# naswietlarka.net
KiCad netlist of a schematic drawn in EAGLE
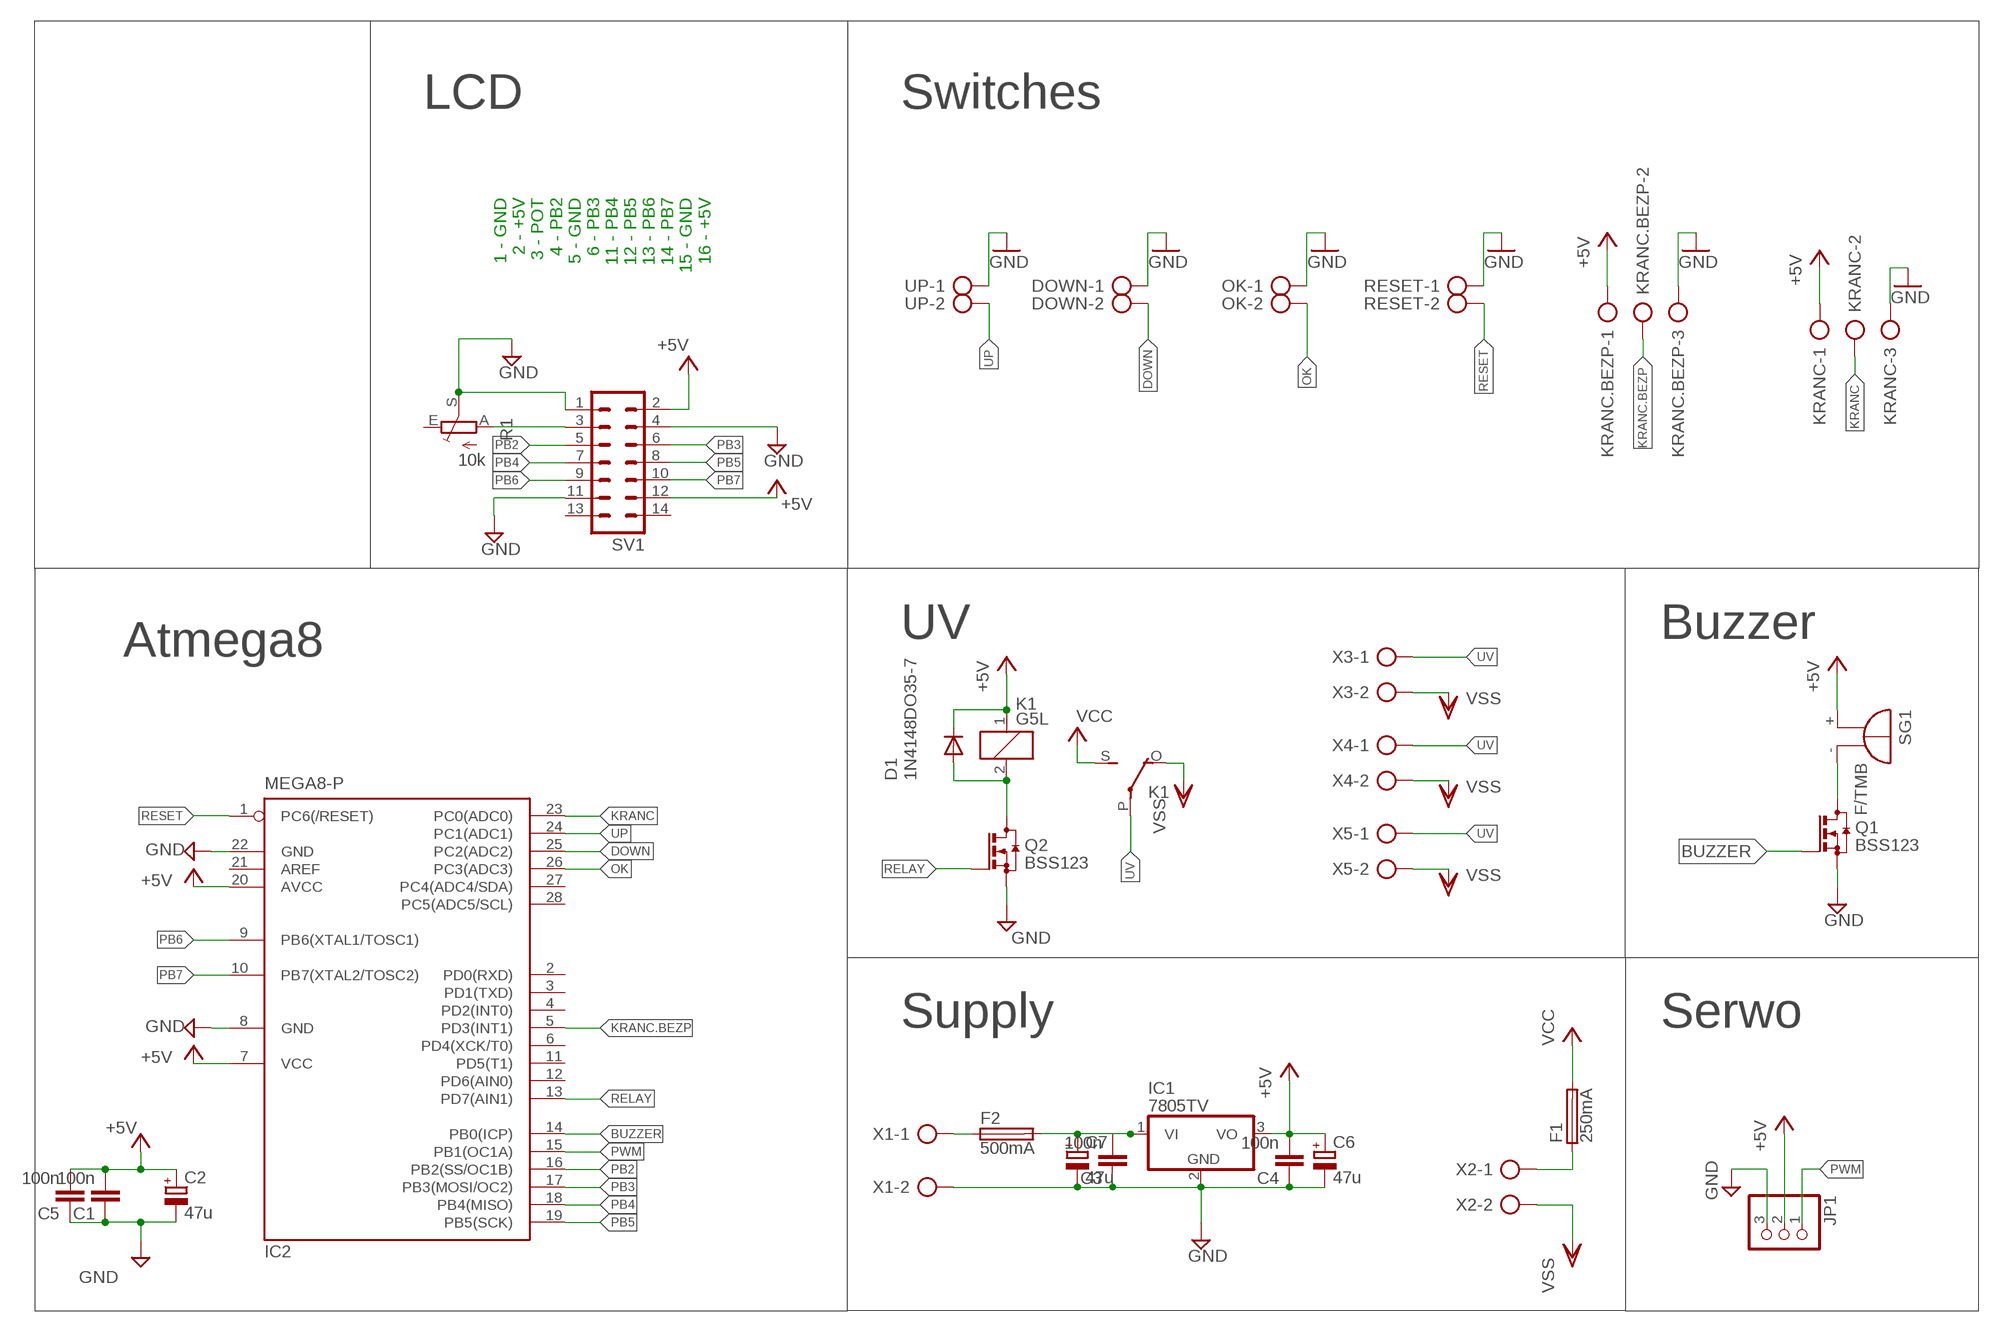
[diagram p0: schematic, sheet 1]

(export (version "E")
  (design (tool "Eeschema 10.0.6"))
  (components
    (comp (ref "C1")
      (value "100n")
      (footprint "eagle-import:C0805")
      (libsource (lib "eagle-import") (part "C-EUC0805"))
    )
    (comp (ref "C2")
      (value "47u")
      (footprint "eagle-import:E2,5-5")
      (libsource (lib "eagle-import") (part "CPOL-EUE2.5-5"))
    )
    (comp (ref "C3")
      (value "100n")
      (footprint "eagle-import:C0805")
      (libsource (lib "eagle-import") (part "C-EUC0805"))
    )
    (comp (ref "C4")
      (value "100n")
      (footprint "eagle-import:C0805")
      (libsource (lib "eagle-import") (part "C-EUC0805"))
    )
    (comp (ref "C5")
      (value "100n")
      (footprint "eagle-import:C0805")
      (libsource (lib "eagle-import") (part "C-EUC0805"))
    )
    (comp (ref "C6")
      (value "47u")
      (footprint "eagle-import:E2,5-5")
      (libsource (lib "eagle-import") (part "CPOL-EUE2.5-5"))
    )
    (comp (ref "C7")
      (value "47u")
      (footprint "eagle-import:E2,5-5")
      (libsource (lib "eagle-import") (part "CPOL-EUE2.5-5"))
    )
    (comp (ref "D1")
      (value "1N4148DO35-7")
      (footprint "eagle-import:DO35-7")
      (libsource (lib "eagle-import") (part "1N4148DO35-7"))
    )
    (comp (ref "DOWN")
      (value "AK300/2")
      (footprint "eagle-import:AK300_2")
      (libsource (lib "eagle-import") (part "AK300/2"))
    )
    (comp (ref "F1")
      (value "250mA")
      (footprint "eagle-import:SH22,5")
      (fields (field (name "MF") "SCHURTER") (field (name "MPN") "0031.8201"))
      (libsource (lib "eagle-import") (part "SH22,5"))
    )
    (comp (ref "F2")
      (value "500mA")
      (footprint "eagle-import:SH22,5")
      (fields (field (name "MF") "SCHURTER") (field (name "MPN") "0031.8201"))
      (libsource (lib "eagle-import") (part "SH22,5"))
    )
    (comp (ref "IC1")
      (value "7805TV")
      (footprint "eagle-import:TO220V")
      (libsource (lib "eagle-import") (part "78TV05"))
    )
    (comp (ref "IC2")
      (value "MEGA8-P")
      (footprint "eagle-import:DIL28-3")
      (libsource (lib "eagle-import") (part "MEGA8-P"))
    )
    (comp (ref "JP1")
      (value "PINHD-1X3")
      (footprint "eagle-import:1X03")
      (libsource (lib "eagle-import") (part "PINHD-1X3"))
    )
    (comp (ref "K1")
      (value "G5L")
      (footprint "eagle-import:G5LE")
      (libsource (lib "eagle-import") (part "G5L"))
    )
    (comp (ref "KRANC")
      (value "AK300/3")
      (footprint "eagle-import:AK300_3")
      (libsource (lib "eagle-import") (part "AK300/3"))
    )
    (comp (ref "KRANC.BEZP")
      (value "AK300/3")
      (footprint "eagle-import:AK300_3")
      (libsource (lib "eagle-import") (part "AK300/3"))
    )
    (comp (ref "OK")
      (value "AK300/2")
      (footprint "eagle-import:AK300_2")
      (libsource (lib "eagle-import") (part "AK300/2"))
    )
    (comp (ref "Q1")
      (value "BSS123")
      (footprint "eagle-import:SOT23")
      (libsource (lib "eagle-import") (part "BSS123"))
    )
    (comp (ref "Q2")
      (value "BSS123")
      (footprint "eagle-import:SOT23")
      (libsource (lib "eagle-import") (part "BSS123"))
    )
    (comp (ref "R1")
      (value "10k")
      (footprint "eagle-import:CA6V")
      (libsource (lib "eagle-import") (part "TRIM_EU-CA6V"))
    )
    (comp (ref "RESET")
      (value "AK300/2")
      (footprint "eagle-import:AK300_2")
      (libsource (lib "eagle-import") (part "AK300/2"))
    )
    (comp (ref "SG1")
      (value "F/TMB")
      (footprint "eagle-import:F_TMB")
      (libsource (lib "eagle-import") (part "F/TMB"))
    )
    (comp (ref "SV1")
      (value "ML14")
      (footprint "eagle-import:ML14")
      (libsource (lib "eagle-import") (part "ML14"))
    )
    (comp (ref "UP")
      (value "AK300/2")
      (footprint "eagle-import:AK300_2")
      (libsource (lib "eagle-import") (part "AK300/2"))
    )
    (comp (ref "X1")
      (value "AK500/2-H")
      (footprint "eagle-import:AK500_2-H")
      (libsource (lib "eagle-import") (part "AK500/2-H"))
    )
    (comp (ref "X2")
      (value "AK500/2-H")
      (footprint "eagle-import:AK500_2-H")
      (libsource (lib "eagle-import") (part "AK500/2-H"))
    )
    (comp (ref "X3")
      (value "AK500/2-H")
      (footprint "eagle-import:AK500_2-H")
      (libsource (lib "eagle-import") (part "AK500/2-H"))
    )
    (comp (ref "X4")
      (value "AK500/2-H")
      (footprint "eagle-import:AK500_2-H")
      (libsource (lib "eagle-import") (part "AK500/2-H"))
    )
    (comp (ref "X5")
      (value "AK500/2-H")
      (footprint "eagle-import:AK500_2-H")
      (libsource (lib "eagle-import") (part "AK500/2-H"))
    )
  )
  (nets
    (net (code "1") (name "+5V") (class "Default")
      (node (ref "C1") (pin "2") (pinfunction "2_2") (pintype "passive"))
      (node (ref "C2") (pin "+") (pinfunction "+_+") (pintype "passive"))
      (node (ref "C4") (pin "2") (pinfunction "2_2") (pintype "passive"))
      (node (ref "C5") (pin "2") (pinfunction "2_2") (pintype "passive"))
      (node (ref "C6") (pin "+") (pinfunction "+_+") (pintype "passive"))
      (node (ref "D1") (pin "C") (pinfunction "C_C") (pintype "passive"))
      (node (ref "IC1") (pin "3") (pinfunction "VO_3") (pintype "passive"))
      (node (ref "IC2") (pin "20") (pinfunction "AVCC_20") (pintype "power_in"))
      (node (ref "IC2") (pin "7") (pinfunction "VCC_7") (pintype "power_in"))
      (node (ref "JP1") (pin "2") (pinfunction "2_2") (pintype "passive"))
      (node (ref "K1") (pin "1") (pinfunction "1_1") (pintype "passive"))
      (node (ref "KRANC") (pin "1") (pinfunction "KL_1") (pintype "passive"))
      (node (ref "KRANC.BEZP") (pin "1") (pinfunction "KL_1") (pintype "passive"))
      (node (ref "SG1") (pin "+") (pinfunction "+_+") (pintype "passive"))
      (node (ref "SV1") (pin "12") (pinfunction "12_12") (pintype "passive"))
      (node (ref "SV1") (pin "2") (pinfunction "2_2") (pintype "passive"))
    )
    (net (code "2") (name "BUZZER") (class "Default")
      (node (ref "IC2") (pin "14") (pinfunction "PB0(ICP)_14") (pintype "bidirectional"))
      (node (ref "Q1") (pin "1") (pinfunction "G_1") (pintype "passive"))
    )
    (net (code "3") (name "DOWN") (class "Default")
      (node (ref "DOWN") (pin "2") (pinfunction "KL_2") (pintype "passive"))
      (node (ref "IC2") (pin "25") (pinfunction "PC2(ADC2)_25") (pintype "bidirectional"))
    )
    (net (code "4") (name "GND") (class "Default")
      (node (ref "C1") (pin "1") (pinfunction "1_1") (pintype "passive"))
      (node (ref "C2") (pin "-") (pinfunction "-_-") (pintype "passive"))
      (node (ref "C3") (pin "1") (pinfunction "1_1") (pintype "passive"))
      (node (ref "C4") (pin "1") (pinfunction "1_1") (pintype "passive"))
      (node (ref "C5") (pin "1") (pinfunction "1_1") (pintype "passive"))
      (node (ref "C6") (pin "-") (pinfunction "-_-") (pintype "passive"))
      (node (ref "C7") (pin "-") (pinfunction "-_-") (pintype "passive"))
      (node (ref "DOWN") (pin "1") (pinfunction "KL_1") (pintype "passive"))
      (node (ref "IC1") (pin "2") (pinfunction "GND_2") (pintype "passive"))
      (node (ref "IC2") (pin "22") (pinfunction "GND_22") (pintype "power_in"))
      (node (ref "IC2") (pin "8") (pinfunction "GND_8") (pintype "power_in"))
      (node (ref "JP1") (pin "3") (pinfunction "3_3") (pintype "passive"))
      (node (ref "KRANC") (pin "3") (pinfunction "KL_3") (pintype "passive"))
      (node (ref "KRANC.BEZP") (pin "3") (pinfunction "KL_3") (pintype "passive"))
      (node (ref "OK") (pin "1") (pinfunction "KL_1") (pintype "passive"))
      (node (ref "Q1") (pin "2") (pinfunction "S_2") (pintype "passive"))
      (node (ref "Q2") (pin "2") (pinfunction "S_2") (pintype "passive"))
      (node (ref "R1") (pin "S") (pinfunction "S_S") (pintype "passive"))
      (node (ref "RESET") (pin "1") (pinfunction "KL_1") (pintype "passive"))
      (node (ref "SV1") (pin "1") (pinfunction "1_1") (pintype "passive"))
      (node (ref "SV1") (pin "11") (pinfunction "11_11") (pintype "passive"))
      (node (ref "SV1") (pin "4") (pinfunction "4_4") (pintype "passive"))
      (node (ref "UP") (pin "1") (pinfunction "KL_1") (pintype "passive"))
      (node (ref "X1") (pin "2") (pinfunction "KL_2") (pintype "passive"))
    )
    (net (code "5") (name "KRANC") (class "Default")
      (node (ref "IC2") (pin "23") (pinfunction "PC0(ADC0)_23") (pintype "bidirectional"))
      (node (ref "KRANC") (pin "2") (pinfunction "KL_2") (pintype "passive"))
    )
    (net (code "6") (name "KRANC.BEZP") (class "Default")
      (node (ref "IC2") (pin "5") (pinfunction "PD3(INT1)_5") (pintype "bidirectional"))
      (node (ref "KRANC.BEZP") (pin "2") (pinfunction "KL_2") (pintype "passive"))
    )
    (net (code "7") (name "Net-(IC1-VI)") (class "Default")
      (node (ref "C3") (pin "2") (pinfunction "2_2") (pintype "passive"))
      (node (ref "C7") (pin "+") (pinfunction "+_+") (pintype "passive"))
      (node (ref "F2") (pin "2") (pinfunction "2_2") (pintype "passive"))
      (node (ref "IC1") (pin "1") (pinfunction "VI_1") (pintype "input"))
    )
    (net (code "8") (name "Net-(Q1-D)") (class "Default")
      (node (ref "Q1") (pin "3") (pinfunction "D_3") (pintype "passive"))
      (node (ref "SG1") (pin "-") (pinfunction "-_-") (pintype "passive"))
    )
    (net (code "9") (name "Net-(Q2-D)") (class "Default")
      (node (ref "D1") (pin "A") (pinfunction "A_A") (pintype "passive"))
      (node (ref "K1") (pin "2") (pinfunction "2_2") (pintype "passive"))
      (node (ref "Q2") (pin "3") (pinfunction "D_3") (pintype "passive"))
    )
    (net (code "10") (name "Net-(R1-PadA)") (class "Default")
      (node (ref "R1") (pin "A") (pinfunction "A_A") (pintype "passive"))
      (node (ref "SV1") (pin "3") (pinfunction "3_3") (pintype "passive"))
    )
    (net (code "11") (name "Net-(X1A-KL)") (class "Default")
      (node (ref "F2") (pin "1") (pinfunction "1_1") (pintype "passive"))
      (node (ref "X1") (pin "1") (pinfunction "KL_1") (pintype "passive"))
    )
    (net (code "12") (name "Net-(X2A-KL)") (class "Default")
      (node (ref "F1") (pin "1") (pinfunction "1_1") (pintype "passive"))
      (node (ref "X2") (pin "1") (pinfunction "KL_1") (pintype "passive"))
    )
    (net (code "13") (name "OK") (class "Default")
      (node (ref "IC2") (pin "26") (pinfunction "PC3(ADC3)_26") (pintype "bidirectional"))
      (node (ref "OK") (pin "2") (pinfunction "KL_2") (pintype "passive"))
    )
    (net (code "14") (name "PB2") (class "Default")
      (node (ref "IC2") (pin "16") (pinfunction "PB2(SS/OC1B)_16") (pintype "bidirectional"))
      (node (ref "SV1") (pin "5") (pinfunction "5_5") (pintype "passive"))
    )
    (net (code "15") (name "PB3") (class "Default")
      (node (ref "IC2") (pin "17") (pinfunction "PB3(MOSI/OC2)_17") (pintype "bidirectional"))
      (node (ref "SV1") (pin "6") (pinfunction "6_6") (pintype "passive"))
    )
    (net (code "16") (name "PB4") (class "Default")
      (node (ref "IC2") (pin "18") (pinfunction "PB4(MISO)_18") (pintype "bidirectional"))
      (node (ref "SV1") (pin "7") (pinfunction "7_7") (pintype "passive"))
    )
    (net (code "17") (name "PB5") (class "Default")
      (node (ref "IC2") (pin "19") (pinfunction "PB5(SCK)_19") (pintype "bidirectional"))
      (node (ref "SV1") (pin "8") (pinfunction "8_8") (pintype "passive"))
    )
    (net (code "18") (name "PB6") (class "Default")
      (node (ref "IC2") (pin "9") (pinfunction "PB6(XTAL1/TOSC1)_9") (pintype "bidirectional"))
      (node (ref "SV1") (pin "9") (pinfunction "9_9") (pintype "passive"))
    )
    (net (code "19") (name "PB7") (class "Default")
      (node (ref "IC2") (pin "10") (pinfunction "PB7(XTAL2/TOSC2)_10") (pintype "bidirectional"))
      (node (ref "SV1") (pin "10") (pinfunction "10_10") (pintype "passive"))
    )
    (net (code "20") (name "PWM") (class "Default")
      (node (ref "IC2") (pin "15") (pinfunction "PB1(OC1A)_15") (pintype "bidirectional"))
      (node (ref "JP1") (pin "1") (pinfunction "1_1") (pintype "passive"))
    )
    (net (code "21") (name "RELAY") (class "Default")
      (node (ref "IC2") (pin "13") (pinfunction "PD7(AIN1)_13") (pintype "bidirectional"))
      (node (ref "Q2") (pin "1") (pinfunction "G_1") (pintype "passive"))
    )
    (net (code "22") (name "RESET") (class "Default")
      (node (ref "IC2") (pin "1") (pinfunction "PC6(/RESET)_1") (pintype "bidirectional"))
      (node (ref "RESET") (pin "2") (pinfunction "KL_2") (pintype "passive"))
    )
    (net (code "23") (name "UP") (class "Default")
      (node (ref "IC2") (pin "24") (pinfunction "PC1(ADC1)_24") (pintype "bidirectional"))
      (node (ref "UP") (pin "2") (pinfunction "KL_2") (pintype "passive"))
    )
    (net (code "24") (name "UV") (class "Default")
      (node (ref "K1") (pin "P") (pinfunction "P_P") (pintype "passive"))
      (node (ref "X3") (pin "1") (pinfunction "KL_1") (pintype "passive"))
      (node (ref "X4") (pin "1") (pinfunction "KL_1") (pintype "passive"))
      (node (ref "X5") (pin "1") (pinfunction "KL_1") (pintype "passive"))
    )
    (net (code "25") (name "VCC") (class "Default")
      (node (ref "F1") (pin "2") (pinfunction "2_2") (pintype "passive"))
      (node (ref "K1") (pin "S") (pinfunction "S_S") (pintype "passive"))
    )
    (net (code "26") (name "VSS") (class "Default")
      (node (ref "K1") (pin "O") (pinfunction "O_O") (pintype "passive"))
      (node (ref "X2") (pin "2") (pinfunction "KL_2") (pintype "passive"))
      (node (ref "X3") (pin "2") (pinfunction "KL_2") (pintype "passive"))
      (node (ref "X4") (pin "2") (pinfunction "KL_2") (pintype "passive"))
      (node (ref "X5") (pin "2") (pinfunction "KL_2") (pintype "passive"))
    )
    (net (code "27") (name "unconnected-(IC2-AREF-Pad21)") (class "Default")
      (node (ref "IC2") (pin "21") (pinfunction "AREF_21") (pintype "passive"))
    )
    (net (code "28") (name "unconnected-(IC2-PC4(ADC4{slash}SDA)-Pad27)") (class "Default")
      (node (ref "IC2") (pin "27") (pinfunction "PC4(ADC4/SDA)_27") (pintype "bidirectional"))
    )
    (net (code "29") (name "unconnected-(IC2-PC5(ADC5{slash}SCL)-Pad28)") (class "Default")
      (node (ref "IC2") (pin "28") (pinfunction "PC5(ADC5/SCL)_28") (pintype "bidirectional"))
    )
    (net (code "30") (name "unconnected-(IC2-PD0(RXD)-Pad2)") (class "Default")
      (node (ref "IC2") (pin "2") (pinfunction "PD0(RXD)_2") (pintype "bidirectional"))
    )
    (net (code "31") (name "unconnected-(IC2-PD1(TXD)-Pad3)") (class "Default")
      (node (ref "IC2") (pin "3") (pinfunction "PD1(TXD)_3") (pintype "bidirectional"))
    )
    (net (code "32") (name "unconnected-(IC2-PD2(INT0)-Pad4)") (class "Default")
      (node (ref "IC2") (pin "4") (pinfunction "PD2(INT0)_4") (pintype "bidirectional"))
    )
    (net (code "33") (name "unconnected-(IC2-PD4(XCK{slash}T0)-Pad6)") (class "Default")
      (node (ref "IC2") (pin "6") (pinfunction "PD4(XCK/T0)_6") (pintype "bidirectional"))
    )
    (net (code "34") (name "unconnected-(IC2-PD5(T1)-Pad11)") (class "Default")
      (node (ref "IC2") (pin "11") (pinfunction "PD5(T1)_11") (pintype "bidirectional"))
    )
    (net (code "35") (name "unconnected-(IC2-PD6(AIN0)-Pad12)") (class "Default")
      (node (ref "IC2") (pin "12") (pinfunction "PD6(AIN0)_12") (pintype "bidirectional"))
    )
    (net (code "36") (name "unconnected-(R1-PadE)") (class "Default")
      (node (ref "R1") (pin "E") (pinfunction "E_E") (pintype "passive"))
    )
    (net (code "37") (name "unconnected-(SV1-Pad13)") (class "Default")
      (node (ref "SV1") (pin "13") (pinfunction "13_13") (pintype "passive"))
    )
    (net (code "38") (name "unconnected-(SV1-Pad14)") (class "Default")
      (node (ref "SV1") (pin "14") (pinfunction "14_14") (pintype "passive"))
    )
  )
)
